# Sheet1.net
KiCad netlist of a schematic drawn in Altium Designer
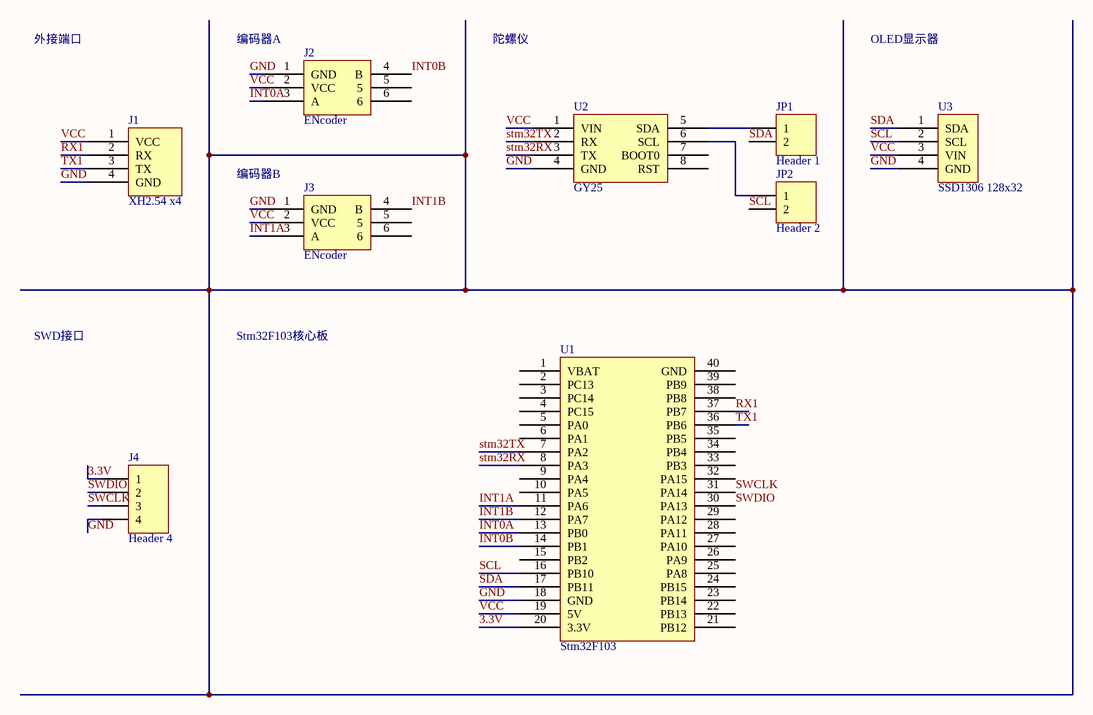
[diagram p0: Sheet1.SchDoc]

(export (version "E")
  (design (tool "Eeschema 10.0.6"))
  (components
    (comp (ref "J1")
      (value "XH2.54 x4")
      (footprint "XH2.54")
      (libsource (lib "Integrated_Library1") (part "XH2.54 x4"))
    )
    (comp (ref "J2")
      (value "ENcoder")
      (footprint "6pin2")
      (libsource (lib "Integrated_Library1") (part "ENcoder"))
    )
    (comp (ref "J3")
      (value "ENcoder")
      (footprint "6pin2")
      (libsource (lib "Integrated_Library1") (part "ENcoder"))
    )
    (comp (ref "J4")
      (value "Header 4")
      (footprint "HDR1X4")
      (description "Header, 4-Pin")
      (fields (field (name "PUBLISHER") "Altium Limited"))
      (libsource (lib "Miscellaneous Connectors") (part "Header 4"))
    )
    (comp (ref "JP1")
      (value "Header 1")
      (footprint "HDR1X2")
      (description "Header, 2-Pin")
      (fields (field (name "PUBLISHER") "Altium Limited"))
      (libsource (lib "Miscellaneous Connectors") (part "Header 2"))
    )
    (comp (ref "JP2")
      (value "Header 2")
      (footprint "HDR1X2")
      (description "Header, 2-Pin")
      (fields (field (name "PUBLISHER") "Altium Limited"))
      (libsource (lib "Miscellaneous Connectors") (part "Header 2"))
    )
    (comp (ref "U1")
      (value "Stm32F103")
      (footprint "STM32F103C8T6-4")
      (libsource (lib "STM32F103C8T6原理图库文件") (part "Component_1"))
    )
    (comp (ref "U2")
      (value "GY25")
      (footprint "PCBComponent_1")
      (libsource (lib "Integrated_Library1") (part "GY25"))
    )
    (comp (ref "U3")
      (value "SSD1306 128x32")
      (footprint "SSD1306 iic")
      (libsource (lib "Integrated_Library1") (part "SSD1306 128x32"))
    )
  )
  (nets
    (net (code "1") (name "/3.3V") (class "Default")
      (node (ref "J4") (pin "1") (pinfunction "1_1") (pintype "passive"))
      (node (ref "U1") (pin "20") (pinfunction "3.3V_20") (pintype "passive"))
    )
    (net (code "2") (name "/GND") (class "Default")
      (node (ref "J1") (pin "4") (pinfunction "GND_4") (pintype "passive"))
      (node (ref "J2") (pin "1") (pinfunction "GND_1") (pintype "passive"))
      (node (ref "J3") (pin "1") (pinfunction "GND_1") (pintype "passive"))
      (node (ref "J4") (pin "4") (pinfunction "4_4") (pintype "passive"))
      (node (ref "U1") (pin "18") (pinfunction "GND_18") (pintype "passive"))
      (node (ref "U2") (pin "4") (pinfunction "GND_4") (pintype "passive"))
      (node (ref "U3") (pin "4") (pinfunction "GND_4") (pintype "passive"))
    )
    (net (code "3") (name "/INT0A") (class "Default")
      (node (ref "J2") (pin "3") (pinfunction "A_3") (pintype "passive"))
      (node (ref "U1") (pin "13") (pinfunction "PB0_13") (pintype "passive"))
    )
    (net (code "4") (name "/INT0B") (class "Default")
      (node (ref "J2") (pin "4") (pinfunction "B_4") (pintype "passive"))
      (node (ref "U1") (pin "14") (pinfunction "PB1_14") (pintype "passive"))
    )
    (net (code "5") (name "/INT1A") (class "Default")
      (node (ref "J3") (pin "3") (pinfunction "A_3") (pintype "passive"))
      (node (ref "U1") (pin "11") (pinfunction "PA6_11") (pintype "passive"))
    )
    (net (code "6") (name "/INT1B") (class "Default")
      (node (ref "J3") (pin "4") (pinfunction "B_4") (pintype "passive"))
      (node (ref "U1") (pin "12") (pinfunction "PA7_12") (pintype "passive"))
    )
    (net (code "7") (name "/RX1") (class "Default")
      (node (ref "J1") (pin "2") (pinfunction "RX_2") (pintype "passive"))
      (node (ref "U1") (pin "37") (pinfunction "PB7_37") (pintype "passive"))
    )
    (net (code "8") (name "/SCL") (class "Default")
      (node (ref "JP2") (pin "2") (pinfunction "2_2") (pintype "passive"))
      (node (ref "U1") (pin "16") (pinfunction "PB10_16") (pintype "passive"))
      (node (ref "U3") (pin "2") (pinfunction "SCL_2") (pintype "passive"))
    )
    (net (code "9") (name "/SDA") (class "Default")
      (node (ref "JP1") (pin "2") (pinfunction "2_2") (pintype "passive"))
      (node (ref "U1") (pin "17") (pinfunction "PB11_17") (pintype "passive"))
      (node (ref "U3") (pin "1") (pinfunction "SDA_1") (pintype "passive"))
    )
    (net (code "10") (name "/SWCLK") (class "Default")
      (node (ref "J4") (pin "3") (pinfunction "3_3") (pintype "passive"))
      (node (ref "U1") (pin "31") (pinfunction "PA14_31") (pintype "passive"))
    )
    (net (code "11") (name "/SWDIO") (class "Default")
      (node (ref "J4") (pin "2") (pinfunction "2_2") (pintype "passive"))
      (node (ref "U1") (pin "30") (pinfunction "PA13_30") (pintype "passive"))
    )
    (net (code "12") (name "/TX1") (class "Default")
      (node (ref "J1") (pin "3") (pinfunction "TX_3") (pintype "passive"))
      (node (ref "U1") (pin "36") (pinfunction "PB6_36") (pintype "passive"))
    )
    (net (code "13") (name "/VCC") (class "Default")
      (node (ref "J1") (pin "1") (pinfunction "VCC_1") (pintype "passive"))
      (node (ref "J2") (pin "2") (pinfunction "VCC_2") (pintype "passive"))
      (node (ref "J3") (pin "2") (pinfunction "VCC_2") (pintype "passive"))
      (node (ref "U1") (pin "19") (pinfunction "5V_19") (pintype "passive"))
      (node (ref "U2") (pin "1") (pinfunction "VIN_1") (pintype "passive"))
      (node (ref "U3") (pin "3") (pinfunction "VIN_3") (pintype "passive"))
    )
    (net (code "14") (name "/stm32RX") (class "Default")
      (node (ref "U1") (pin "8") (pinfunction "PA3_8") (pintype "passive"))
      (node (ref "U2") (pin "3") (pinfunction "TX_3") (pintype "passive"))
    )
    (net (code "15") (name "/stm32TX") (class "Default")
      (node (ref "U1") (pin "7") (pinfunction "PA2_7") (pintype "passive"))
      (node (ref "U2") (pin "2") (pinfunction "RX_2") (pintype "passive"))
    )
    (net (code "16") (name "Net-(U2-SCL)") (class "Default")
      (node (ref "JP2") (pin "1") (pinfunction "1_1") (pintype "passive"))
      (node (ref "U2") (pin "6") (pinfunction "SCL_6") (pintype "passive"))
    )
    (net (code "17") (name "Net-(U2-SDA)") (class "Default")
      (node (ref "JP1") (pin "1") (pinfunction "1_1") (pintype "passive"))
      (node (ref "U2") (pin "5") (pinfunction "SDA_5") (pintype "passive"))
    )
    (net (code "18") (name "unconnected-(J2-Pad5)") (class "Default")
      (node (ref "J2") (pin "5") (pinfunction "5_5") (pintype "passive"))
    )
    (net (code "19") (name "unconnected-(J2-Pad6)") (class "Default")
      (node (ref "J2") (pin "6") (pinfunction "6_6") (pintype "passive"))
    )
    (net (code "20") (name "unconnected-(J3-Pad5)") (class "Default")
      (node (ref "J3") (pin "5") (pinfunction "5_5") (pintype "passive"))
    )
    (net (code "21") (name "unconnected-(J3-Pad6)") (class "Default")
      (node (ref "J3") (pin "6") (pinfunction "6_6") (pintype "passive"))
    )
    (net (code "22") (name "unconnected-(U1-GND-Pad40)") (class "Default")
      (node (ref "U1") (pin "40") (pinfunction "GND_40") (pintype "passive"))
    )
    (net (code "23") (name "unconnected-(U1-PA0-Pad5)") (class "Default")
      (node (ref "U1") (pin "5") (pinfunction "PA0_5") (pintype "passive"))
    )
    (net (code "24") (name "unconnected-(U1-PA1-Pad6)") (class "Default")
      (node (ref "U1") (pin "6") (pinfunction "PA1_6") (pintype "passive"))
    )
    (net (code "25") (name "unconnected-(U1-PA4-Pad9)") (class "Default")
      (node (ref "U1") (pin "9") (pinfunction "PA4_9") (pintype "passive"))
    )
    (net (code "26") (name "unconnected-(U1-PA5-Pad10)") (class "Default")
      (node (ref "U1") (pin "10") (pinfunction "PA5_10") (pintype "passive"))
    )
    (net (code "27") (name "unconnected-(U1-PA8-Pad25)") (class "Default")
      (node (ref "U1") (pin "25") (pinfunction "PA8_25") (pintype "passive"))
    )
    (net (code "28") (name "unconnected-(U1-PA9-Pad26)") (class "Default")
      (node (ref "U1") (pin "26") (pinfunction "PA9_26") (pintype "passive"))
    )
    (net (code "29") (name "unconnected-(U1-PA10-Pad27)") (class "Default")
      (node (ref "U1") (pin "27") (pinfunction "PA10_27") (pintype "passive"))
    )
    (net (code "30") (name "unconnected-(U1-PA11-Pad28)") (class "Default")
      (node (ref "U1") (pin "28") (pinfunction "PA11_28") (pintype "passive"))
    )
    (net (code "31") (name "unconnected-(U1-PA12-Pad29)") (class "Default")
      (node (ref "U1") (pin "29") (pinfunction "PA12_29") (pintype "passive"))
    )
    (net (code "32") (name "unconnected-(U1-PA15-Pad32)") (class "Default")
      (node (ref "U1") (pin "32") (pinfunction "PA15_32") (pintype "passive"))
    )
    (net (code "33") (name "unconnected-(U1-PB2-Pad15)") (class "Default")
      (node (ref "U1") (pin "15") (pinfunction "PB2_15") (pintype "passive"))
    )
    (net (code "34") (name "unconnected-(U1-PB3-Pad33)") (class "Default")
      (node (ref "U1") (pin "33") (pinfunction "PB3_33") (pintype "passive"))
    )
    (net (code "35") (name "unconnected-(U1-PB4-Pad34)") (class "Default")
      (node (ref "U1") (pin "34") (pinfunction "PB4_34") (pintype "passive"))
    )
    (net (code "36") (name "unconnected-(U1-PB5-Pad35)") (class "Default")
      (node (ref "U1") (pin "35") (pinfunction "PB5_35") (pintype "passive"))
    )
    (net (code "37") (name "unconnected-(U1-PB8-Pad38)") (class "Default")
      (node (ref "U1") (pin "38") (pinfunction "PB8_38") (pintype "passive"))
    )
    (net (code "38") (name "unconnected-(U1-PB9-Pad39)") (class "Default")
      (node (ref "U1") (pin "39") (pinfunction "PB9_39") (pintype "passive"))
    )
    (net (code "39") (name "unconnected-(U1-PB12-Pad21)") (class "Default")
      (node (ref "U1") (pin "21") (pinfunction "PB12_21") (pintype "passive"))
    )
    (net (code "40") (name "unconnected-(U1-PB13-Pad22)") (class "Default")
      (node (ref "U1") (pin "22") (pinfunction "PB13_22") (pintype "passive"))
    )
    (net (code "41") (name "unconnected-(U1-PB14-Pad23)") (class "Default")
      (node (ref "U1") (pin "23") (pinfunction "PB14_23") (pintype "passive"))
    )
    (net (code "42") (name "unconnected-(U1-PB15-Pad24)") (class "Default")
      (node (ref "U1") (pin "24") (pinfunction "PB15_24") (pintype "passive"))
    )
    (net (code "43") (name "unconnected-(U1-PC13-Pad2)") (class "Default")
      (node (ref "U1") (pin "2") (pinfunction "PC13_2") (pintype "passive"))
    )
    (net (code "44") (name "unconnected-(U1-PC14-Pad3)") (class "Default")
      (node (ref "U1") (pin "3") (pinfunction "PC14_3") (pintype "passive"))
    )
    (net (code "45") (name "unconnected-(U1-PC15-Pad4)") (class "Default")
      (node (ref "U1") (pin "4") (pinfunction "PC15_4") (pintype "passive"))
    )
    (net (code "46") (name "unconnected-(U1-VBAT-Pad1)") (class "Default")
      (node (ref "U1") (pin "1") (pinfunction "VBAT_1") (pintype "passive"))
    )
    (net (code "47") (name "unconnected-(U2-BOOT0-Pad7)") (class "Default")
      (node (ref "U2") (pin "7") (pinfunction "BOOT0_7") (pintype "passive"))
    )
    (net (code "48") (name "unconnected-(U2-RST-Pad8)") (class "Default")
      (node (ref "U2") (pin "8") (pinfunction "RST_8") (pintype "passive"))
    )
  )
)
